# Repeat_MPPT_charger_1_2.net
KiCad netlist of a schematic drawn in Altium Designer
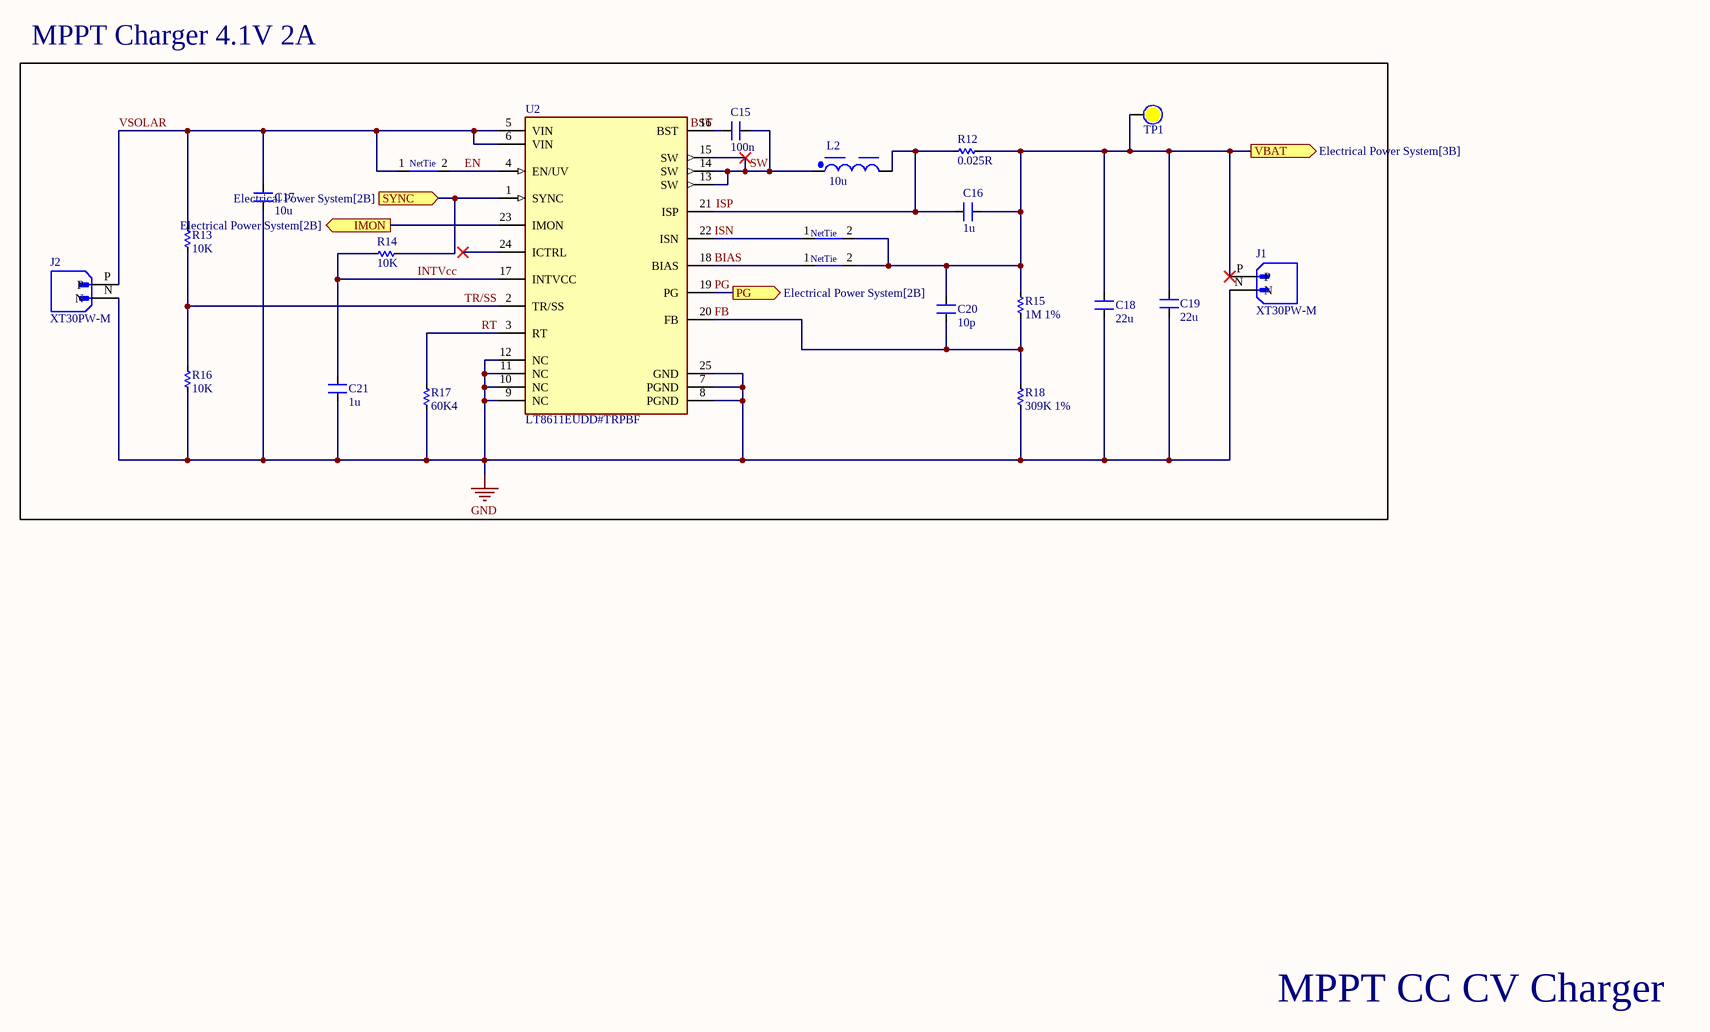
[diagram p0: Repeat(MPPT_charger,1, 2).SchDoc]

(export (version "E")
  (design (tool "Eeschema 10.0.6"))
  (components
    (comp (ref "C15")
      (value "100n")
      (footprint "CN-SMD-0603")
      (libsource (lib "Sang_library") (part "Capacitors"))
    )
    (comp (ref "C16")
      (value "1u")
      (footprint "CN-SMD-0603")
      (libsource (lib "Sang_library") (part "Capacitors"))
    )
    (comp (ref "C17")
      (value "10u")
      (footprint "CN-SMD-1206")
      (libsource (lib "Sang_library") (part "Capacitors"))
    )
    (comp (ref "C18")
      (value "22u")
      (footprint "CN-SMD-1206")
      (libsource (lib "Sang_library") (part "Capacitors"))
    )
    (comp (ref "C19")
      (value "22u")
      (footprint "CN-SMD-1206")
      (libsource (lib "Sang_library") (part "Capacitors"))
    )
    (comp (ref "C20")
      (value "10p")
      (footprint "CN-SMD-0603")
      (libsource (lib "Sang_library") (part "Capacitors"))
    )
    (comp (ref "C21")
      (value "1u")
      (footprint "CN-SMD-0603")
      (libsource (lib "Sang_library") (part "Capacitors"))
    )
    (comp (ref "J1")
      (value "XT30PW-M")
      (footprint "AMASS_XT30PW-M")
      (description "Socket; DC supply; XT30; male; PIN: 2; on PCBs; THT; Colour: yellow")
      (fields (field (name "MF") "AMASS"))
      (libsource (lib "") (part "XT30PW-M_1"))
    )
    (comp (ref "J2")
      (value "XT30PW-M")
      (footprint "AMASS_XT30PW-M")
      (description "Socket; DC supply; XT30; male; PIN: 2; on PCBs; THT; Colour: yellow")
      (fields (field (name "MF") "AMASS"))
      (libsource (lib "XT30PW-M") (part "XT30PW-M"))
    )
    (comp (ref "L2")
      (value "10u")
      (footprint "WE-PD_7345")
      (fields (field (name "TOLERANCE") "20%"))
      (libsource (lib "Altium Content Vault") (part "Inductor - 2"))
    )
    (comp (ref "NT1")
      (value "NetTie")
      (footprint "NETTIE_SMD")
      (description "Net Tie SMD")
      (libsource (lib "Schematic-Lib-PhilsLab") (part "NetTie_SMD"))
    )
    (comp (ref "NT2")
      (value "NetTie")
      (footprint "NETTIE_SMD")
      (description "Net Tie SMD")
      (libsource (lib "Schematic-Lib-PhilsLab") (part "NetTie_SMD"))
    )
    (comp (ref "NT3")
      (value "NetTie")
      (footprint "NETTIE_SMD")
      (description "Net Tie SMD")
      (libsource (lib "Schematic-Lib-PhilsLab") (part "NetTie_SMD"))
    )
    (comp (ref "R12")
      (value "0.025R")
      (footprint "RES-SMD-0805")
      (description "SMD")
      (fields
        (field (name "MANUFACTURER") "Generic Components")
        (field (name "PUBLISHER") "Altium Hobart Technology Centre")
      )
      (libsource (lib "Sang_library") (part "Res SMD"))
    )
    (comp (ref "R13")
      (value "10K")
      (footprint "RES-SMD-0805")
      (description "SMD")
      (fields
        (field (name "MANUFACTURER") "Generic Components")
        (field (name "PUBLISHER") "Altium Hobart Technology Centre")
      )
      (libsource (lib "Sang_library") (part "Res SMD"))
    )
    (comp (ref "R14")
      (value "10K")
      (footprint "RES-SMD-0805")
      (description "SMD")
      (fields
        (field (name "MANUFACTURER") "Generic Components")
        (field (name "PUBLISHER") "Altium Hobart Technology Centre")
      )
      (libsource (lib "Sang_library") (part "Res SMD"))
    )
    (comp (ref "R15")
      (value "1M 1%")
      (footprint "RES-SMD-0805")
      (description "SMD")
      (fields
        (field (name "MANUFACTURER") "Generic Components")
        (field (name "PUBLISHER") "Altium Hobart Technology Centre")
      )
      (libsource (lib "Sang_library") (part "Res SMD"))
    )
    (comp (ref "R16")
      (value "10K")
      (footprint "RES-SMD-0805")
      (description "SMD")
      (fields
        (field (name "MANUFACTURER") "Generic Components")
        (field (name "PUBLISHER") "Altium Hobart Technology Centre")
      )
      (libsource (lib "Sang_library") (part "Res SMD"))
    )
    (comp (ref "R17")
      (value "60K4")
      (footprint "RES-SMD-0805")
      (description "SMD")
      (fields
        (field (name "MANUFACTURER") "Generic Components")
        (field (name "PUBLISHER") "Altium Hobart Technology Centre")
      )
      (libsource (lib "Sang_library") (part "Res SMD"))
    )
    (comp (ref "R18")
      (value "309K 1%")
      (footprint "RES-SMD-0805")
      (description "SMD")
      (fields
        (field (name "MANUFACTURER") "Generic Components")
        (field (name "PUBLISHER") "Altium Hobart Technology Centre")
      )
      (libsource (lib "Sang_library") (part "Res SMD"))
    )
    (comp (ref "TP1")
      (value "TestPoint")
      (footprint "Test Point 1 MM")
      (description "Test Point")
      (libsource (lib "Sang_library") (part "Test Point"))
    )
    (comp (ref "U2")
      (value "LT8611EUDD#TRPBF")
      (footprint "FP-UDD-24-05-08-1833-IPC_B")
      (description "IC REG BUCK ADJ 2.5A 24QFN")
      (libsource (lib "Altium Content Vault") (part "fa917c90ce6974f84498b26f3756de5"))
    )
  )
  (nets
    (net (code "1") (name "/BIAS") (class "Default")
      (node (ref "NT3") (pin "1") (pinfunction "1_1") (pintype "passive"))
      (node (ref "U2") (pin "18") (pinfunction "BIAS_18") (pintype "passive"))
    )
    (net (code "2") (name "/BST") (class "Default")
      (node (ref "C15") (pin "2") (pinfunction "2_2") (pintype "passive"))
      (node (ref "U2") (pin "16") (pinfunction "BST_16") (pintype "passive"))
    )
    (net (code "3") (name "/EN") (class "Default")
      (node (ref "NT1") (pin "2") (pinfunction "2_2") (pintype "passive"))
      (node (ref "U2") (pin "4") (pinfunction "EN/UV_4") (pintype "input"))
    )
    (net (code "4") (name "/FB") (class "Default")
      (node (ref "C20") (pin "1") (pinfunction "1_1") (pintype "passive"))
      (node (ref "R15") (pin "2") (pinfunction "2_2") (pintype "passive"))
      (node (ref "R18") (pin "1") (pinfunction "1_1") (pintype "passive"))
      (node (ref "U2") (pin "20") (pinfunction "FB_20") (pintype "passive"))
    )
    (net (code "5") (name "/IMON") (class "Default")
      (node (ref "U2") (pin "23") (pinfunction "IMON_23") (pintype "passive"))
    )
    (net (code "6") (name "/INTVcc") (class "Default")
      (node (ref "C21") (pin "2") (pinfunction "2_2") (pintype "passive"))
      (node (ref "R14") (pin "2") (pinfunction "2_2") (pintype "passive"))
      (node (ref "U2") (pin "17") (pinfunction "INTVCC_17") (pintype "passive"))
    )
    (net (code "7") (name "/ISN") (class "Default")
      (node (ref "NT2") (pin "1") (pinfunction "1_1") (pintype "passive"))
      (node (ref "U2") (pin "22") (pinfunction "ISN_22") (pintype "passive"))
    )
    (net (code "8") (name "/ISP") (class "Default")
      (node (ref "C16") (pin "2") (pinfunction "2_2") (pintype "passive"))
      (node (ref "L2") (pin "2") (pinfunction "2_2") (pintype "passive"))
      (node (ref "R12") (pin "2") (pinfunction "2_2") (pintype "passive"))
      (node (ref "U2") (pin "21") (pinfunction "ISP_21") (pintype "passive"))
    )
    (net (code "9") (name "/PG") (class "Default")
      (node (ref "U2") (pin "19") (pinfunction "PG_19") (pintype "passive"))
    )
    (net (code "10") (name "/RT") (class "Default")
      (node (ref "R17") (pin "2") (pinfunction "2_2") (pintype "passive"))
      (node (ref "U2") (pin "3") (pinfunction "RT_3") (pintype "passive"))
    )
    (net (code "11") (name "/SW") (class "Default")
      (node (ref "C15") (pin "1") (pinfunction "1_1") (pintype "passive"))
      (node (ref "L2") (pin "1") (pinfunction "1_1") (pintype "passive"))
      (node (ref "U2") (pin "13") (pinfunction "SW_13") (pintype "output"))
      (node (ref "U2") (pin "14") (pinfunction "SW_14") (pintype "output"))
      (node (ref "U2") (pin "15") (pinfunction "SW_15") (pintype "output"))
    )
    (net (code "12") (name "/SYNC") (class "Default")
      (node (ref "R14") (pin "1") (pinfunction "1_1") (pintype "passive"))
      (node (ref "U2") (pin "1") (pinfunction "SYNC_1") (pintype "input"))
    )
    (net (code "13") (name "/TR{slash}SS") (class "Default")
      (node (ref "R13") (pin "1") (pinfunction "1_1") (pintype "passive"))
      (node (ref "R16") (pin "2") (pinfunction "2_2") (pintype "passive"))
      (node (ref "U2") (pin "2") (pinfunction "TR/SS_2") (pintype "passive"))
    )
    (net (code "14") (name "/VBAT") (class "Default")
      (node (ref "C16") (pin "1") (pinfunction "1_1") (pintype "passive"))
      (node (ref "C18") (pin "2") (pinfunction "2_2") (pintype "passive"))
      (node (ref "C19") (pin "2") (pinfunction "2_2") (pintype "passive"))
      (node (ref "C20") (pin "2") (pinfunction "2_2") (pintype "passive"))
      (node (ref "J1") (pin "P") (pinfunction "P_P") (pintype "power_in"))
      (node (ref "NT2") (pin "2") (pinfunction "2_2") (pintype "passive"))
      (node (ref "NT3") (pin "2") (pinfunction "2_2") (pintype "passive"))
      (node (ref "R12") (pin "1") (pinfunction "1_1") (pintype "passive"))
      (node (ref "R15") (pin "1") (pinfunction "1_1") (pintype "passive"))
      (node (ref "TP1") (pin "0") (pinfunction "0_0") (pintype "passive"))
    )
    (net (code "15") (name "/VSOLAR") (class "Default")
      (node (ref "C17") (pin "2") (pinfunction "2_2") (pintype "passive"))
      (node (ref "J2") (pin "P") (pinfunction "P_P") (pintype "power_in"))
      (node (ref "NT1") (pin "1") (pinfunction "1_1") (pintype "passive"))
      (node (ref "R13") (pin "2") (pinfunction "2_2") (pintype "passive"))
      (node (ref "U2") (pin "5") (pinfunction "VIN_5") (pintype "power_in"))
      (node (ref "U2") (pin "6") (pinfunction "VIN_6") (pintype "power_in"))
    )
    (net (code "16") (name "GND") (class "Default")
      (node (ref "C17") (pin "1") (pinfunction "1_1") (pintype "passive"))
      (node (ref "C18") (pin "1") (pinfunction "1_1") (pintype "passive"))
      (node (ref "C19") (pin "1") (pinfunction "1_1") (pintype "passive"))
      (node (ref "C21") (pin "1") (pinfunction "1_1") (pintype "passive"))
      (node (ref "J1") (pin "N") (pinfunction "N_N") (pintype "power_in"))
      (node (ref "J2") (pin "N") (pinfunction "N_N") (pintype "power_in"))
      (node (ref "R16") (pin "1") (pinfunction "1_1") (pintype "passive"))
      (node (ref "R17") (pin "1") (pinfunction "1_1") (pintype "passive"))
      (node (ref "R18") (pin "2") (pinfunction "2_2") (pintype "passive"))
      (node (ref "U2") (pin "10") (pinfunction "NC_10") (pintype "passive"))
      (node (ref "U2") (pin "11") (pinfunction "NC_11") (pintype "passive"))
      (node (ref "U2") (pin "12") (pinfunction "NC_12") (pintype "passive"))
      (node (ref "U2") (pin "25") (pinfunction "GND_25") (pintype "power_in"))
      (node (ref "U2") (pin "7") (pinfunction "PGND_7") (pintype "power_in"))
      (node (ref "U2") (pin "8") (pinfunction "PGND_8") (pintype "power_in"))
      (node (ref "U2") (pin "9") (pinfunction "NC_9") (pintype "passive"))
    )
    (net (code "17") (name "unconnected-(U2-ICTRL-Pad24)") (class "Default")
      (node (ref "U2") (pin "24") (pinfunction "ICTRL_24") (pintype "passive+no_connect"))
    )
  )
)
